# CENTRAL_HUB_MODIFIED.net
KiCad netlist of a schematic drawn in EAGLE
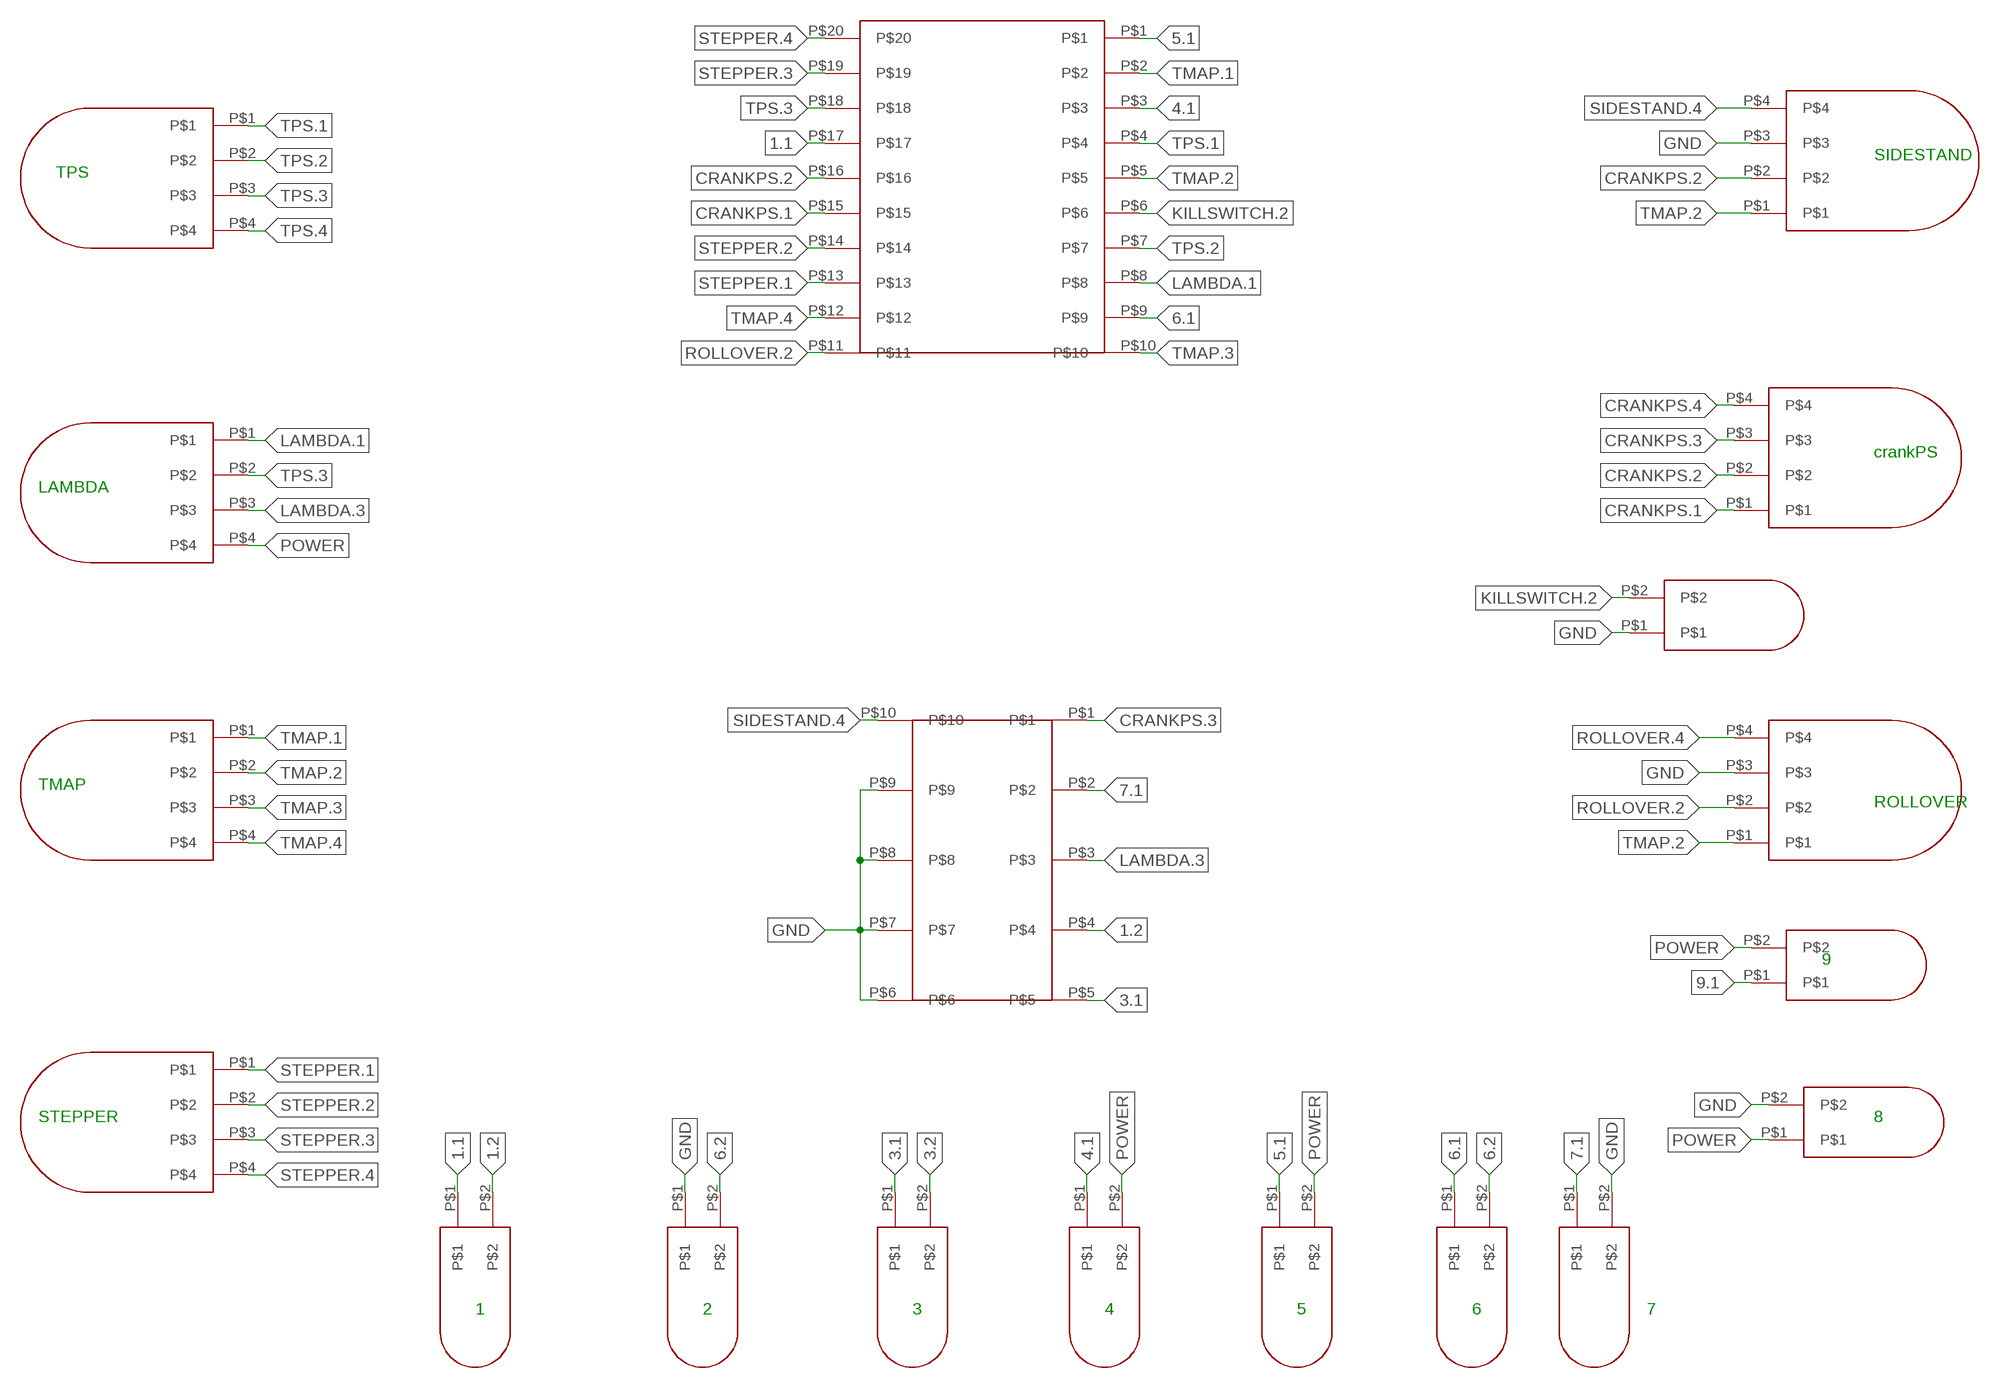
[diagram p0: schematic, sheet 1]

(export (version "E")
  (design (tool "Eeschema 10.0.6"))
  (components
    (comp (ref "1")
      (value "2-PIN")
      (footprint "eagle-import:2PIN")
      (libsource (lib "eagle-import") (part "2-PIN"))
    )
    (comp (ref "2")
      (value "2-PIN")
      (footprint "eagle-import:2PIN")
      (libsource (lib "eagle-import") (part "2-PIN"))
    )
    (comp (ref "3")
      (value "2-PIN")
      (footprint "eagle-import:2PIN")
      (libsource (lib "eagle-import") (part "2-PIN"))
    )
    (comp (ref "4")
      (value "2-PIN")
      (footprint "eagle-import:2PIN")
      (libsource (lib "eagle-import") (part "2-PIN"))
    )
    (comp (ref "5")
      (value "2-PIN")
      (footprint "eagle-import:2PIN")
      (libsource (lib "eagle-import") (part "2-PIN"))
    )
    (comp (ref "6")
      (value "2-PIN")
      (footprint "eagle-import:2PIN")
      (libsource (lib "eagle-import") (part "2-PIN"))
    )
    (comp (ref "7")
      (value "2-PIN")
      (footprint "eagle-import:2PIN")
      (libsource (lib "eagle-import") (part "2-PIN"))
    )
    (comp (ref "8")
      (value "2-PIN")
      (footprint "eagle-import:2PIN")
      (libsource (lib "eagle-import") (part "2-PIN"))
    )
    (comp (ref "9")
      (value "2-PIN")
      (footprint "eagle-import:2PIN")
      (libsource (lib "eagle-import") (part "2-PIN"))
    )
    (comp (ref "CRANK")
      (value "4-PIN")
      (footprint "eagle-import:4PIN")
      (libsource (lib "eagle-import") (part "4-PIN"))
    )
    (comp (ref "KILLSWITCH")
      (value "2-PIN")
      (footprint "eagle-import:2PIN")
      (libsource (lib "eagle-import") (part "2-PIN"))
    )
    (comp (ref "LAMBDA")
      (value "4-PIN")
      (footprint "eagle-import:4PIN")
      (libsource (lib "eagle-import") (part "4-PIN"))
    )
    (comp (ref "ROLLOVER")
      (value "4-PIN")
      (footprint "eagle-import:4PIN")
      (libsource (lib "eagle-import") (part "4-PIN"))
    )
    (comp (ref "SIDESTAND")
      (value "4-PIN")
      (footprint "eagle-import:4PIN")
      (libsource (lib "eagle-import") (part "4-PIN"))
    )
    (comp (ref "STEPPER")
      (value "4-PIN")
      (footprint "eagle-import:4PIN")
      (libsource (lib "eagle-import") (part "4-PIN"))
    )
    (comp (ref "TMAP")
      (value "4-PIN")
      (footprint "eagle-import:4PIN")
      (libsource (lib "eagle-import") (part "4-PIN"))
    )
    (comp (ref "TPS")
      (value "4-PIN")
      (footprint "eagle-import:4PIN")
      (libsource (lib "eagle-import") (part "4-PIN"))
    )
    (comp (ref "U$1")
      (value "ECU1-20")
      (footprint "eagle-import:ECU")
      (libsource (lib "eagle-import") (part "ECU1-20"))
    )
    (comp (ref "U$2")
      (value "ECU2-10")
      (footprint "eagle-import:10PIN")
      (libsource (lib "eagle-import") (part "ECU2-10"))
    )
  )
  (nets
    (net (code "1") (name "1.1") (class "Default")
      (node (ref "1") (pin "P$1") (pinfunction "P$1_P$1") (pintype "bidirectional"))
      (node (ref "U$1") (pin "P$17") (pinfunction "P$17_P$17") (pintype "bidirectional"))
    )
    (net (code "2") (name "1.2") (class "Default")
      (node (ref "1") (pin "P$2") (pinfunction "P$2_P$2") (pintype "bidirectional"))
      (node (ref "U$2") (pin "P$4") (pinfunction "P$4_P$4") (pintype "bidirectional"))
    )
    (net (code "3") (name "3.1") (class "Default")
      (node (ref "3") (pin "P$1") (pinfunction "P$1_P$1") (pintype "bidirectional"))
      (node (ref "U$2") (pin "P$5") (pinfunction "P$5_P$5") (pintype "bidirectional"))
    )
    (net (code "4") (name "3.2") (class "Default")
      (node (ref "3") (pin "P$2") (pinfunction "P$2_P$2") (pintype "bidirectional"))
    )
    (net (code "5") (name "4.1") (class "Default")
      (node (ref "4") (pin "P$1") (pinfunction "P$1_P$1") (pintype "bidirectional"))
      (node (ref "U$1") (pin "P$3") (pinfunction "P$3_P$3") (pintype "bidirectional"))
    )
    (net (code "6") (name "5.1") (class "Default")
      (node (ref "5") (pin "P$1") (pinfunction "P$1_P$1") (pintype "bidirectional"))
      (node (ref "U$1") (pin "P$1") (pinfunction "P$1_P$1") (pintype "bidirectional"))
    )
    (net (code "7") (name "6.1") (class "Default")
      (node (ref "6") (pin "P$1") (pinfunction "P$1_P$1") (pintype "bidirectional"))
      (node (ref "U$1") (pin "P$9") (pinfunction "P$9_P$9") (pintype "bidirectional"))
    )
    (net (code "8") (name "6.2") (class "Default")
      (node (ref "2") (pin "P$2") (pinfunction "P$2_P$2") (pintype "bidirectional"))
      (node (ref "6") (pin "P$2") (pinfunction "P$2_P$2") (pintype "bidirectional"))
    )
    (net (code "9") (name "7.1") (class "Default")
      (node (ref "7") (pin "P$1") (pinfunction "P$1_P$1") (pintype "bidirectional"))
      (node (ref "U$2") (pin "P$2") (pinfunction "P$2_P$2") (pintype "bidirectional"))
    )
    (net (code "10") (name "9.1") (class "Default")
      (node (ref "9") (pin "P$1") (pinfunction "P$1_P$1") (pintype "bidirectional"))
    )
    (net (code "11") (name "CRANKPS.1") (class "Default")
      (node (ref "CRANK") (pin "P$1") (pinfunction "P$1_P$1") (pintype "bidirectional"))
      (node (ref "U$1") (pin "P$15") (pinfunction "P$15_P$15") (pintype "bidirectional"))
    )
    (net (code "12") (name "CRANKPS.2") (class "Default")
      (node (ref "CRANK") (pin "P$2") (pinfunction "P$2_P$2") (pintype "bidirectional"))
      (node (ref "SIDESTAND") (pin "P$2") (pinfunction "P$2_P$2") (pintype "bidirectional"))
      (node (ref "U$1") (pin "P$16") (pinfunction "P$16_P$16") (pintype "bidirectional"))
    )
    (net (code "13") (name "CRANKPS.3") (class "Default")
      (node (ref "CRANK") (pin "P$3") (pinfunction "P$3_P$3") (pintype "bidirectional"))
      (node (ref "U$2") (pin "P$1") (pinfunction "P$1_P$1") (pintype "bidirectional"))
    )
    (net (code "14") (name "CRANKPS.4") (class "Default")
      (node (ref "CRANK") (pin "P$4") (pinfunction "P$4_P$4") (pintype "bidirectional"))
    )
    (net (code "15") (name "GND") (class "Default")
      (node (ref "2") (pin "P$1") (pinfunction "P$1_P$1") (pintype "bidirectional"))
      (node (ref "7") (pin "P$2") (pinfunction "P$2_P$2") (pintype "bidirectional"))
      (node (ref "8") (pin "P$2") (pinfunction "P$2_P$2") (pintype "bidirectional"))
      (node (ref "KILLSWITCH") (pin "P$1") (pinfunction "P$1_P$1") (pintype "bidirectional"))
      (node (ref "ROLLOVER") (pin "P$3") (pinfunction "P$3_P$3") (pintype "bidirectional"))
      (node (ref "SIDESTAND") (pin "P$3") (pinfunction "P$3_P$3") (pintype "bidirectional"))
      (node (ref "U$2") (pin "P$6") (pinfunction "P$6_P$6") (pintype "bidirectional"))
      (node (ref "U$2") (pin "P$7") (pinfunction "P$7_P$7") (pintype "bidirectional"))
      (node (ref "U$2") (pin "P$8") (pinfunction "P$8_P$8") (pintype "bidirectional"))
      (node (ref "U$2") (pin "P$9") (pinfunction "P$9_P$9") (pintype "bidirectional"))
    )
    (net (code "16") (name "KILLSWITCH.2") (class "Default")
      (node (ref "KILLSWITCH") (pin "P$2") (pinfunction "P$2_P$2") (pintype "bidirectional"))
      (node (ref "U$1") (pin "P$6") (pinfunction "P$6_P$6") (pintype "bidirectional"))
    )
    (net (code "17") (name "LAMBDA.1") (class "Default")
      (node (ref "LAMBDA") (pin "P$1") (pinfunction "P$1_P$1") (pintype "bidirectional"))
      (node (ref "U$1") (pin "P$8") (pinfunction "P$8_P$8") (pintype "bidirectional"))
    )
    (net (code "18") (name "LAMBDA.3") (class "Default")
      (node (ref "LAMBDA") (pin "P$3") (pinfunction "P$3_P$3") (pintype "bidirectional"))
      (node (ref "U$2") (pin "P$3") (pinfunction "P$3_P$3") (pintype "bidirectional"))
    )
    (net (code "19") (name "POWER") (class "Default")
      (node (ref "4") (pin "P$2") (pinfunction "P$2_P$2") (pintype "bidirectional"))
      (node (ref "5") (pin "P$2") (pinfunction "P$2_P$2") (pintype "bidirectional"))
      (node (ref "8") (pin "P$1") (pinfunction "P$1_P$1") (pintype "bidirectional"))
      (node (ref "9") (pin "P$2") (pinfunction "P$2_P$2") (pintype "bidirectional"))
      (node (ref "LAMBDA") (pin "P$4") (pinfunction "P$4_P$4") (pintype "bidirectional"))
    )
    (net (code "20") (name "ROLLOVER.2") (class "Default")
      (node (ref "ROLLOVER") (pin "P$2") (pinfunction "P$2_P$2") (pintype "bidirectional"))
      (node (ref "U$1") (pin "P$11") (pinfunction "P$11_P$11") (pintype "bidirectional"))
    )
    (net (code "21") (name "ROLLOVER.4") (class "Default")
      (node (ref "ROLLOVER") (pin "P$4") (pinfunction "P$4_P$4") (pintype "bidirectional"))
    )
    (net (code "22") (name "SIDESTAND.4") (class "Default")
      (node (ref "SIDESTAND") (pin "P$4") (pinfunction "P$4_P$4") (pintype "bidirectional"))
      (node (ref "U$2") (pin "P$10") (pinfunction "P$10_P$10") (pintype "bidirectional"))
    )
    (net (code "23") (name "STEPPER.1") (class "Default")
      (node (ref "STEPPER") (pin "P$1") (pinfunction "P$1_P$1") (pintype "bidirectional"))
      (node (ref "U$1") (pin "P$13") (pinfunction "P$13_P$13") (pintype "bidirectional"))
    )
    (net (code "24") (name "STEPPER.2") (class "Default")
      (node (ref "STEPPER") (pin "P$2") (pinfunction "P$2_P$2") (pintype "bidirectional"))
      (node (ref "U$1") (pin "P$14") (pinfunction "P$14_P$14") (pintype "bidirectional"))
    )
    (net (code "25") (name "STEPPER.3") (class "Default")
      (node (ref "STEPPER") (pin "P$3") (pinfunction "P$3_P$3") (pintype "bidirectional"))
      (node (ref "U$1") (pin "P$19") (pinfunction "P$19_P$19") (pintype "bidirectional"))
    )
    (net (code "26") (name "STEPPER.4") (class "Default")
      (node (ref "STEPPER") (pin "P$4") (pinfunction "P$4_P$4") (pintype "bidirectional"))
      (node (ref "U$1") (pin "P$20") (pinfunction "P$20_P$20") (pintype "bidirectional"))
    )
    (net (code "27") (name "TMAP.1") (class "Default")
      (node (ref "TMAP") (pin "P$1") (pinfunction "P$1_P$1") (pintype "bidirectional"))
      (node (ref "U$1") (pin "P$2") (pinfunction "P$2_P$2") (pintype "bidirectional"))
    )
    (net (code "28") (name "TMAP.2") (class "Default")
      (node (ref "ROLLOVER") (pin "P$1") (pinfunction "P$1_P$1") (pintype "bidirectional"))
      (node (ref "SIDESTAND") (pin "P$1") (pinfunction "P$1_P$1") (pintype "bidirectional"))
      (node (ref "TMAP") (pin "P$2") (pinfunction "P$2_P$2") (pintype "bidirectional"))
      (node (ref "U$1") (pin "P$5") (pinfunction "P$5_P$5") (pintype "bidirectional"))
    )
    (net (code "29") (name "TMAP.3") (class "Default")
      (node (ref "TMAP") (pin "P$3") (pinfunction "P$3_P$3") (pintype "bidirectional"))
      (node (ref "U$1") (pin "P$10") (pinfunction "P$10_P$10") (pintype "bidirectional"))
    )
    (net (code "30") (name "TMAP.4") (class "Default")
      (node (ref "TMAP") (pin "P$4") (pinfunction "P$4_P$4") (pintype "bidirectional"))
      (node (ref "U$1") (pin "P$12") (pinfunction "P$12_P$12") (pintype "bidirectional"))
    )
    (net (code "31") (name "TPS.1") (class "Default")
      (node (ref "TPS") (pin "P$1") (pinfunction "P$1_P$1") (pintype "bidirectional"))
      (node (ref "U$1") (pin "P$4") (pinfunction "P$4_P$4") (pintype "bidirectional"))
    )
    (net (code "32") (name "TPS.2") (class "Default")
      (node (ref "TPS") (pin "P$2") (pinfunction "P$2_P$2") (pintype "bidirectional"))
      (node (ref "U$1") (pin "P$7") (pinfunction "P$7_P$7") (pintype "bidirectional"))
    )
    (net (code "33") (name "TPS.3") (class "Default")
      (node (ref "LAMBDA") (pin "P$2") (pinfunction "P$2_P$2") (pintype "bidirectional"))
      (node (ref "TPS") (pin "P$3") (pinfunction "P$3_P$3") (pintype "bidirectional"))
      (node (ref "U$1") (pin "P$18") (pinfunction "P$18_P$18") (pintype "bidirectional"))
    )
    (net (code "34") (name "TPS.4") (class "Default")
      (node (ref "TPS") (pin "P$4") (pinfunction "P$4_P$4") (pintype "bidirectional"))
    )
  )
)
